# Memory_EEPROM.net
KiCad netlist of a schematic drawn in Altium Designer
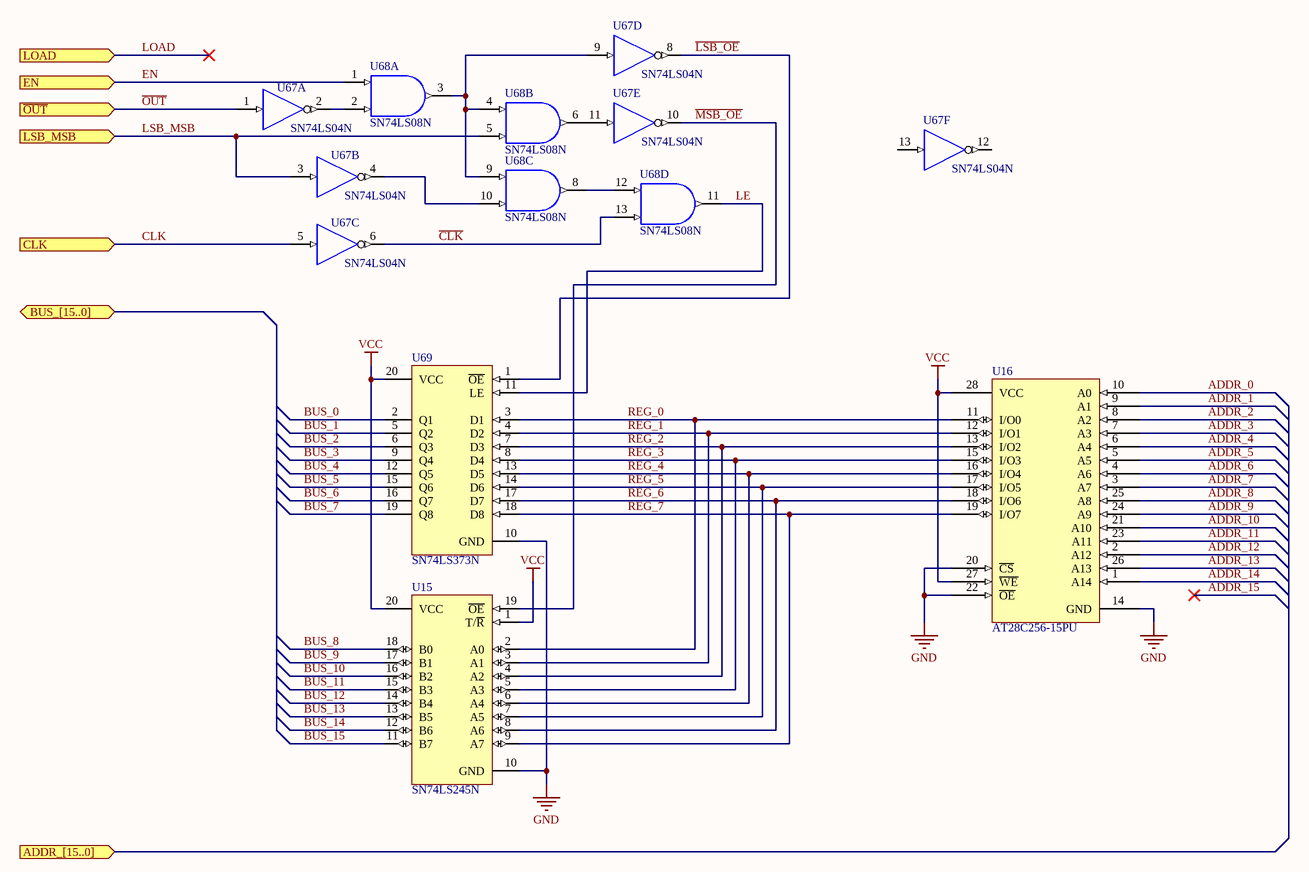
[diagram p0: Memory_EEPROM.SchDoc]

(export (version "E")
  (design (tool "Eeschema 10.0.6"))
  (components
    (comp (ref "U15")
      (value "SN74LS245N")
      (footprint "N020")
      (description "Octal Bus Transceiver with 3-State Outputs")
      (fields (field (name "PUBLISHER") "Altium Limited"))
      (libsource (lib "TI Interface 8-Bit Line Transceiver") (part "SN74LS245N"))
    )
    (comp (ref "U16")
      (value "AT28C256-15PU")
      (footprint "J028")
      (libsource (lib "Schlib1") (part "AT28C256-15PU"))
    )
    (comp (ref "U67")
      (value "SN74LS04N")
      (footprint "N014")
      (description "Hex Inverter")
      (fields (field (name "PUBLISHER") "Altium Limited"))
      (libsource (lib "TI Logic Gate 2") (part "SN74LS04N"))
    )
    (comp (ref "U68")
      (value "SN74LS08N")
      (footprint "N014")
      (description "Quadruple 2-Input Positive-AND Gate")
      (fields (field (name "PUBLISHER") "Altium Limited"))
      (libsource (lib "TI Logic Gate 2") (part "SN74LS08N"))
    )
    (comp (ref "U69")
      (value "SN74LS373N")
      (footprint "N020")
      (description "Octal D-Type Transparent Latche and Edge-Triggered Flip-Flops")
      (fields (field (name "PUBLISHER") "Altium Limited"))
      (libsource (lib "TI Logic Latch") (part "SN74LS373N"))
    )
  )
  (nets
    (net (code "1") (name "/ADDR_0") (class "Default")
      (node (ref "U16") (pin "10") (pinfunction "A0_10") (pintype "input"))
    )
    (net (code "2") (name "/ADDR_1") (class "Default")
      (node (ref "U16") (pin "9") (pinfunction "A1_9") (pintype "input"))
    )
    (net (code "3") (name "/ADDR_2") (class "Default")
      (node (ref "U16") (pin "8") (pinfunction "A2_8") (pintype "input"))
    )
    (net (code "4") (name "/ADDR_3") (class "Default")
      (node (ref "U16") (pin "7") (pinfunction "A3_7") (pintype "input"))
    )
    (net (code "5") (name "/ADDR_4") (class "Default")
      (node (ref "U16") (pin "6") (pinfunction "A4_6") (pintype "input"))
    )
    (net (code "6") (name "/ADDR_5") (class "Default")
      (node (ref "U16") (pin "5") (pinfunction "A5_5") (pintype "input"))
    )
    (net (code "7") (name "/ADDR_6") (class "Default")
      (node (ref "U16") (pin "4") (pinfunction "A6_4") (pintype "input"))
    )
    (net (code "8") (name "/ADDR_7") (class "Default")
      (node (ref "U16") (pin "3") (pinfunction "A7_3") (pintype "input"))
    )
    (net (code "9") (name "/ADDR_8") (class "Default")
      (node (ref "U16") (pin "25") (pinfunction "A8_25") (pintype "input"))
    )
    (net (code "10") (name "/ADDR_9") (class "Default")
      (node (ref "U16") (pin "24") (pinfunction "A9_24") (pintype "input"))
    )
    (net (code "11") (name "/ADDR_10") (class "Default")
      (node (ref "U16") (pin "21") (pinfunction "A10_21") (pintype "input"))
    )
    (net (code "12") (name "/ADDR_11") (class "Default")
      (node (ref "U16") (pin "23") (pinfunction "A11_23") (pintype "input"))
    )
    (net (code "13") (name "/ADDR_12") (class "Default")
      (node (ref "U16") (pin "2") (pinfunction "A12_2") (pintype "input"))
    )
    (net (code "14") (name "/ADDR_13") (class "Default")
      (node (ref "U16") (pin "26") (pinfunction "A13_26") (pintype "input"))
    )
    (net (code "15") (name "/ADDR_14") (class "Default")
      (node (ref "U16") (pin "1") (pinfunction "A14_1") (pintype "input"))
    )
    (net (code "18") (name "/BUS_0") (class "Default")
      (node (ref "U69") (pin "2") (pinfunction "Q1_2") (pintype "tri_state"))
    )
    (net (code "19") (name "/BUS_1") (class "Default")
      (node (ref "U69") (pin "5") (pinfunction "Q2_5") (pintype "tri_state"))
    )
    (net (code "20") (name "/BUS_2") (class "Default")
      (node (ref "U69") (pin "6") (pinfunction "Q3_6") (pintype "tri_state"))
    )
    (net (code "21") (name "/BUS_3") (class "Default")
      (node (ref "U69") (pin "9") (pinfunction "Q4_9") (pintype "tri_state"))
    )
    (net (code "22") (name "/BUS_4") (class "Default")
      (node (ref "U69") (pin "12") (pinfunction "Q5_12") (pintype "tri_state"))
    )
    (net (code "23") (name "/BUS_5") (class "Default")
      (node (ref "U69") (pin "15") (pinfunction "Q6_15") (pintype "tri_state"))
    )
    (net (code "24") (name "/BUS_6") (class "Default")
      (node (ref "U69") (pin "16") (pinfunction "Q7_16") (pintype "tri_state"))
    )
    (net (code "25") (name "/BUS_7") (class "Default")
      (node (ref "U69") (pin "19") (pinfunction "Q8_19") (pintype "tri_state"))
    )
    (net (code "26") (name "/BUS_8") (class "Default")
      (node (ref "U15") (pin "18") (pinfunction "B0_18") (pintype "bidirectional"))
    )
    (net (code "27") (name "/BUS_9") (class "Default")
      (node (ref "U15") (pin "17") (pinfunction "B1_17") (pintype "bidirectional"))
    )
    (net (code "28") (name "/BUS_10") (class "Default")
      (node (ref "U15") (pin "16") (pinfunction "B2_16") (pintype "bidirectional"))
    )
    (net (code "29") (name "/BUS_11") (class "Default")
      (node (ref "U15") (pin "15") (pinfunction "B3_15") (pintype "bidirectional"))
    )
    (net (code "30") (name "/BUS_12") (class "Default")
      (node (ref "U15") (pin "14") (pinfunction "B4_14") (pintype "bidirectional"))
    )
    (net (code "31") (name "/BUS_13") (class "Default")
      (node (ref "U15") (pin "13") (pinfunction "B5_13") (pintype "bidirectional"))
    )
    (net (code "32") (name "/BUS_14") (class "Default")
      (node (ref "U15") (pin "12") (pinfunction "B6_12") (pintype "bidirectional"))
    )
    (net (code "33") (name "/BUS_15") (class "Default")
      (node (ref "U15") (pin "11") (pinfunction "B7_11") (pintype "bidirectional"))
    )
    (net (code "35") (name "/CLK") (class "Default")
      (node (ref "U67") (pin "5") (pinfunction "A_5") (pintype "input"))
    )
    (net (code "36") (name "/EN") (class "Default")
      (node (ref "U68") (pin "1") (pinfunction "A_1") (pintype "input"))
    )
    (net (code "37") (name "/LE") (class "Default")
      (node (ref "U68") (pin "11") (pinfunction "Y_11") (pintype "output"))
      (node (ref "U69") (pin "11") (pinfunction "LE_11") (pintype "input"))
    )
    (net (code "39") (name "/LSB_MSB") (class "Default")
      (node (ref "U67") (pin "3") (pinfunction "A_3") (pintype "input"))
      (node (ref "U68") (pin "5") (pinfunction "B_5") (pintype "input"))
    )
    (net (code "40") (name "/REG_0") (class "Default")
      (node (ref "U15") (pin "2") (pinfunction "A0_2") (pintype "bidirectional"))
      (node (ref "U16") (pin "11") (pinfunction "I/O0_11") (pintype "bidirectional"))
      (node (ref "U69") (pin "3") (pinfunction "D1_3") (pintype "input"))
    )
    (net (code "41") (name "/REG_1") (class "Default")
      (node (ref "U15") (pin "3") (pinfunction "A1_3") (pintype "bidirectional"))
      (node (ref "U16") (pin "12") (pinfunction "I/O1_12") (pintype "bidirectional"))
      (node (ref "U69") (pin "4") (pinfunction "D2_4") (pintype "input"))
    )
    (net (code "42") (name "/REG_2") (class "Default")
      (node (ref "U15") (pin "4") (pinfunction "A2_4") (pintype "bidirectional"))
      (node (ref "U16") (pin "13") (pinfunction "I/O2_13") (pintype "bidirectional"))
      (node (ref "U69") (pin "7") (pinfunction "D3_7") (pintype "input"))
    )
    (net (code "43") (name "/REG_3") (class "Default")
      (node (ref "U15") (pin "5") (pinfunction "A3_5") (pintype "bidirectional"))
      (node (ref "U16") (pin "15") (pinfunction "I/O3_15") (pintype "bidirectional"))
      (node (ref "U69") (pin "8") (pinfunction "D4_8") (pintype "input"))
    )
    (net (code "44") (name "/REG_4") (class "Default")
      (node (ref "U15") (pin "6") (pinfunction "A4_6") (pintype "bidirectional"))
      (node (ref "U16") (pin "16") (pinfunction "I/O4_16") (pintype "bidirectional"))
      (node (ref "U69") (pin "13") (pinfunction "D5_13") (pintype "input"))
    )
    (net (code "45") (name "/REG_5") (class "Default")
      (node (ref "U15") (pin "7") (pinfunction "A5_7") (pintype "bidirectional"))
      (node (ref "U16") (pin "17") (pinfunction "I/O5_17") (pintype "bidirectional"))
      (node (ref "U69") (pin "14") (pinfunction "D6_14") (pintype "input"))
    )
    (net (code "46") (name "/REG_6") (class "Default")
      (node (ref "U15") (pin "8") (pinfunction "A6_8") (pintype "bidirectional"))
      (node (ref "U16") (pin "18") (pinfunction "I/O6_18") (pintype "bidirectional"))
      (node (ref "U69") (pin "17") (pinfunction "D7_17") (pintype "input"))
    )
    (net (code "47") (name "/REG_7") (class "Default")
      (node (ref "U15") (pin "9") (pinfunction "A7_9") (pintype "bidirectional"))
      (node (ref "U16") (pin "19") (pinfunction "I/O7_19") (pintype "bidirectional"))
      (node (ref "U69") (pin "18") (pinfunction "D8_18") (pintype "input"))
    )
    (net (code "48") (name "/~{CLK}") (class "Default")
      (node (ref "U67") (pin "6") (pinfunction "Y_6") (pintype "output"))
      (node (ref "U68") (pin "13") (pinfunction "B_13") (pintype "input"))
    )
    (net (code "49") (name "/~{LSB_OE}") (class "Default")
      (node (ref "U67") (pin "8") (pinfunction "Y_8") (pintype "output"))
      (node (ref "U69") (pin "1") (pinfunction "~{OE}_1") (pintype "input"))
    )
    (net (code "50") (name "/~{MSB_OE}") (class "Default")
      (node (ref "U15") (pin "19") (pinfunction "~{OE}_19") (pintype "input"))
      (node (ref "U67") (pin "10") (pinfunction "Y_10") (pintype "output"))
    )
    (net (code "51") (name "/~{OUT}") (class "Default")
      (node (ref "U67") (pin "1") (pinfunction "A_1") (pintype "input"))
    )
    (net (code "52") (name "GND") (class "Default")
      (node (ref "U15") (pin "10") (pinfunction "GND_10") (pintype "power_in"))
      (node (ref "U16") (pin "14") (pinfunction "GND_14") (pintype "power_in"))
      (node (ref "U16") (pin "20") (pinfunction "~{CS}_20") (pintype "input"))
      (node (ref "U16") (pin "22") (pinfunction "~{OE}_22") (pintype "input"))
      (node (ref "U67") (pin "7") (pinfunction "GND_7") (pintype "power_in"))
      (node (ref "U68") (pin "7") (pinfunction "GND_7") (pintype "power_in"))
      (node (ref "U69") (pin "10") (pinfunction "GND_10") (pintype "power_in"))
    )
    (net (code "53") (name "Net-(U67A-Y)") (class "Default")
      (node (ref "U67") (pin "2") (pinfunction "Y_2") (pintype "output"))
      (node (ref "U68") (pin "2") (pinfunction "B_2") (pintype "input"))
    )
    (net (code "54") (name "Net-(U67B-Y)") (class "Default")
      (node (ref "U67") (pin "4") (pinfunction "Y_4") (pintype "output"))
      (node (ref "U68") (pin "10") (pinfunction "B_10") (pintype "input"))
    )
    (net (code "55") (name "Net-(U67D-A)") (class "Default")
      (node (ref "U67") (pin "9") (pinfunction "A_9") (pintype "input"))
      (node (ref "U68") (pin "3") (pinfunction "Y_3") (pintype "output"))
      (node (ref "U68") (pin "4") (pinfunction "A_4") (pintype "input"))
      (node (ref "U68") (pin "9") (pinfunction "A_9") (pintype "input"))
    )
    (net (code "56") (name "Net-(U67E-A)") (class "Default")
      (node (ref "U67") (pin "11") (pinfunction "A_11") (pintype "input"))
      (node (ref "U68") (pin "6") (pinfunction "Y_6") (pintype "output"))
    )
    (net (code "57") (name "Net-(U68C-Y)") (class "Default")
      (node (ref "U68") (pin "12") (pinfunction "A_12") (pintype "input"))
      (node (ref "U68") (pin "8") (pinfunction "Y_8") (pintype "output"))
    )
    (net (code "58") (name "VCC") (class "Default")
      (node (ref "U15") (pin "1") (pinfunction "T/~{R}_1") (pintype "input"))
      (node (ref "U15") (pin "20") (pinfunction "VCC_20") (pintype "power_in"))
      (node (ref "U16") (pin "27") (pinfunction "~{WE}_27") (pintype "input"))
      (node (ref "U16") (pin "28") (pinfunction "VCC_28") (pintype "power_in"))
      (node (ref "U67") (pin "14") (pinfunction "VCC_14") (pintype "power_in"))
      (node (ref "U68") (pin "14") (pinfunction "VCC_14") (pintype "power_in"))
      (node (ref "U69") (pin "20") (pinfunction "VCC_20") (pintype "power_in"))
    )
    (net (code "59") (name "unconnected-(U67F-A-Pad13)") (class "Default")
      (node (ref "U67") (pin "13") (pinfunction "A_13") (pintype "input"))
    )
    (net (code "60") (name "unconnected-(U67F-Y-Pad12)") (class "Default")
      (node (ref "U67") (pin "12") (pinfunction "Y_12") (pintype "output"))
    )
  )
)
